# InterfacesA_Xbee_Transceiver.net
KiCad netlist of a schematic drawn in Altium Designer
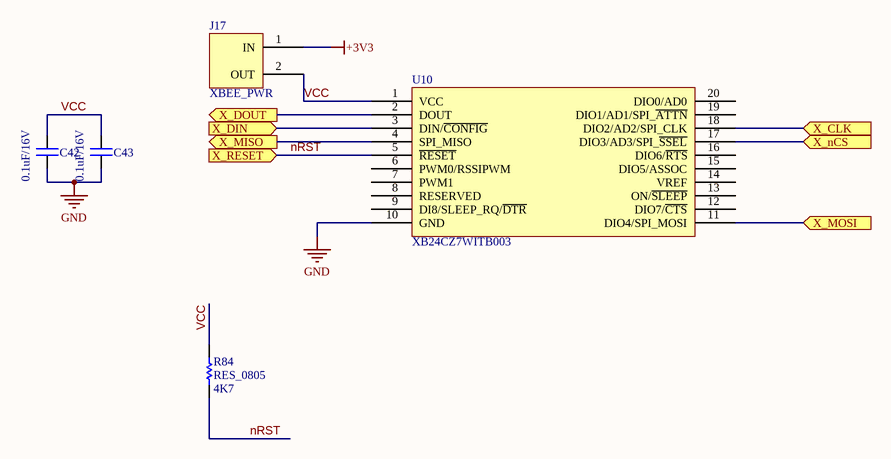
[diagram p0: InterfacesA_Xbee_Transceiver.SchDoc]

(export (version "E")
  (design (tool "Eeschema 10.0.6"))
  (components
    (comp (ref "C42")
      (value "0.1uF/16V")
      (footprint "CAP_0805")
      (fields (field (name "Comment") "CAP_0805"))
      (libsource (lib "LibSGQB") (part "CAP_0603"))
    )
    (comp (ref "C43")
      (value "0.1uF/16V")
      (footprint "CAP_0805")
      (fields (field (name "Comment") "CAP_0805"))
      (libsource (lib "LibSGQB") (part "CAP_0603"))
    )
    (comp (ref "J17")
      (value "XBEE_PWR")
      (footprint "JUMPER 2 PIN")
      (description "JUMPER 2 PIN")
      (libsource (lib "AdapterLib") (part "JUMPER 2 PIN"))
    )
    (comp (ref "R84")
      (value "RES_0805")
      (footprint "RES_0805")
      (fields (field (name "ALTIUM_VALUE") "4K7"))
      (libsource (lib "AdapterLib") (part "RES_0805"))
    )
    (comp (ref "U10")
      (value "XB24CZ7WITB003")
      (footprint "XB24CZ7WITB003")
      (description "XBEE MODULE")
      (libsource (lib "AdapterLib") (part "XB24CZ7WITB003"))
    )
  )
  (nets
    (net (code "1") (name "+3V3") (class "Default")
      (node (ref "J17") (pin "1") (pinfunction "IN_1") (pintype "passive"))
    )
    (net (code "2") (name "/VCC") (class "Default")
      (node (ref "C42") (pin "1") (pinfunction "1_1") (pintype "passive"))
      (node (ref "C43") (pin "1") (pinfunction "1_1") (pintype "passive"))
      (node (ref "J17") (pin "2") (pinfunction "OUT_2") (pintype "passive"))
      (node (ref "R84") (pin "2") (pinfunction "2_2") (pintype "passive"))
      (node (ref "U10") (pin "1") (pinfunction "VCC_1") (pintype "passive"))
    )
    (net (code "3") (name "/X_CLK") (class "Default")
      (node (ref "U10") (pin "18") (pinfunction "DIO2/AD2/SPI_CLK_18") (pintype "passive"))
    )
    (net (code "4") (name "/X_DIN") (class "Default")
      (node (ref "U10") (pin "3") (pinfunction "DIN/~{CONFIG}_3") (pintype "passive"))
    )
    (net (code "5") (name "/X_DOUT") (class "Default")
      (node (ref "U10") (pin "2") (pinfunction "DOUT_2") (pintype "passive"))
    )
    (net (code "6") (name "/X_MISO") (class "Default")
      (node (ref "U10") (pin "4") (pinfunction "SPI_MISO_4") (pintype "passive"))
    )
    (net (code "7") (name "/X_MOSI") (class "Default")
      (node (ref "U10") (pin "11") (pinfunction "DIO4/SPI_MOSI_11") (pintype "passive"))
    )
    (net (code "8") (name "/X_nCS") (class "Default")
      (node (ref "U10") (pin "17") (pinfunction "DIO3/AD3/SPI_~{SSEL}_17") (pintype "passive"))
    )
    (net (code "9") (name "/nRST") (class "Default")
      (node (ref "R84") (pin "1") (pinfunction "1_1") (pintype "passive"))
      (node (ref "U10") (pin "5") (pinfunction "~{RESET}_5") (pintype "passive"))
    )
    (net (code "10") (name "GND") (class "Default")
      (node (ref "C42") (pin "2") (pinfunction "2_2") (pintype "passive"))
      (node (ref "C43") (pin "2") (pinfunction "2_2") (pintype "passive"))
      (node (ref "U10") (pin "10") (pinfunction "GND_10") (pintype "passive"))
    )
    (net (code "11") (name "unconnected-(U10-DI8{slash}SLEEP_RQ{slash}~{DTR}-Pad9)") (class "Default")
      (node (ref "U10") (pin "9") (pinfunction "DI8/SLEEP_RQ/~{DTR}_9") (pintype "passive"))
    )
    (net (code "12") (name "unconnected-(U10-DIO0{slash}AD0-Pad20)") (class "Default")
      (node (ref "U10") (pin "20") (pinfunction "DIO0/AD0_20") (pintype "passive"))
    )
    (net (code "13") (name "unconnected-(U10-DIO1{slash}AD1{slash}SPI_~{ATTN}-Pad19)") (class "Default")
      (node (ref "U10") (pin "19") (pinfunction "DIO1/AD1/SPI_~{ATTN}_19") (pintype "passive"))
    )
    (net (code "14") (name "unconnected-(U10-DIO5{slash}ASSOC-Pad15)") (class "Default")
      (node (ref "U10") (pin "15") (pinfunction "DIO5/ASSOC_15") (pintype "passive"))
    )
    (net (code "15") (name "unconnected-(U10-DIO6{slash}~{RTS}-Pad16)") (class "Default")
      (node (ref "U10") (pin "16") (pinfunction "DIO6/~{RTS}_16") (pintype "passive"))
    )
    (net (code "16") (name "unconnected-(U10-DIO7{slash}~{CTS}-Pad12)") (class "Default")
      (node (ref "U10") (pin "12") (pinfunction "DIO7/~{CTS}_12") (pintype "passive"))
    )
    (net (code "17") (name "unconnected-(U10-ON{slash}~{SLEEP}-Pad13)") (class "Default")
      (node (ref "U10") (pin "13") (pinfunction "ON/~{SLEEP}_13") (pintype "passive"))
    )
    (net (code "18") (name "unconnected-(U10-PWM0{slash}RSSIPWM-Pad6)") (class "Default")
      (node (ref "U10") (pin "6") (pinfunction "PWM0/RSSIPWM_6") (pintype "passive"))
    )
    (net (code "19") (name "unconnected-(U10-PWM1-Pad7)") (class "Default")
      (node (ref "U10") (pin "7") (pinfunction "PWM1_7") (pintype "passive"))
    )
    (net (code "20") (name "unconnected-(U10-RESERVED-Pad8)") (class "Default")
      (node (ref "U10") (pin "8") (pinfunction "RESERVED_8") (pintype "passive"))
    )
    (net (code "21") (name "unconnected-(U10-VREF-Pad14)") (class "Default")
      (node (ref "U10") (pin "14") (pinfunction "VREF_14") (pintype "passive"))
    )
  )
)
